# 10_SDADC.net
KiCad netlist of a schematic drawn in Altium Designer
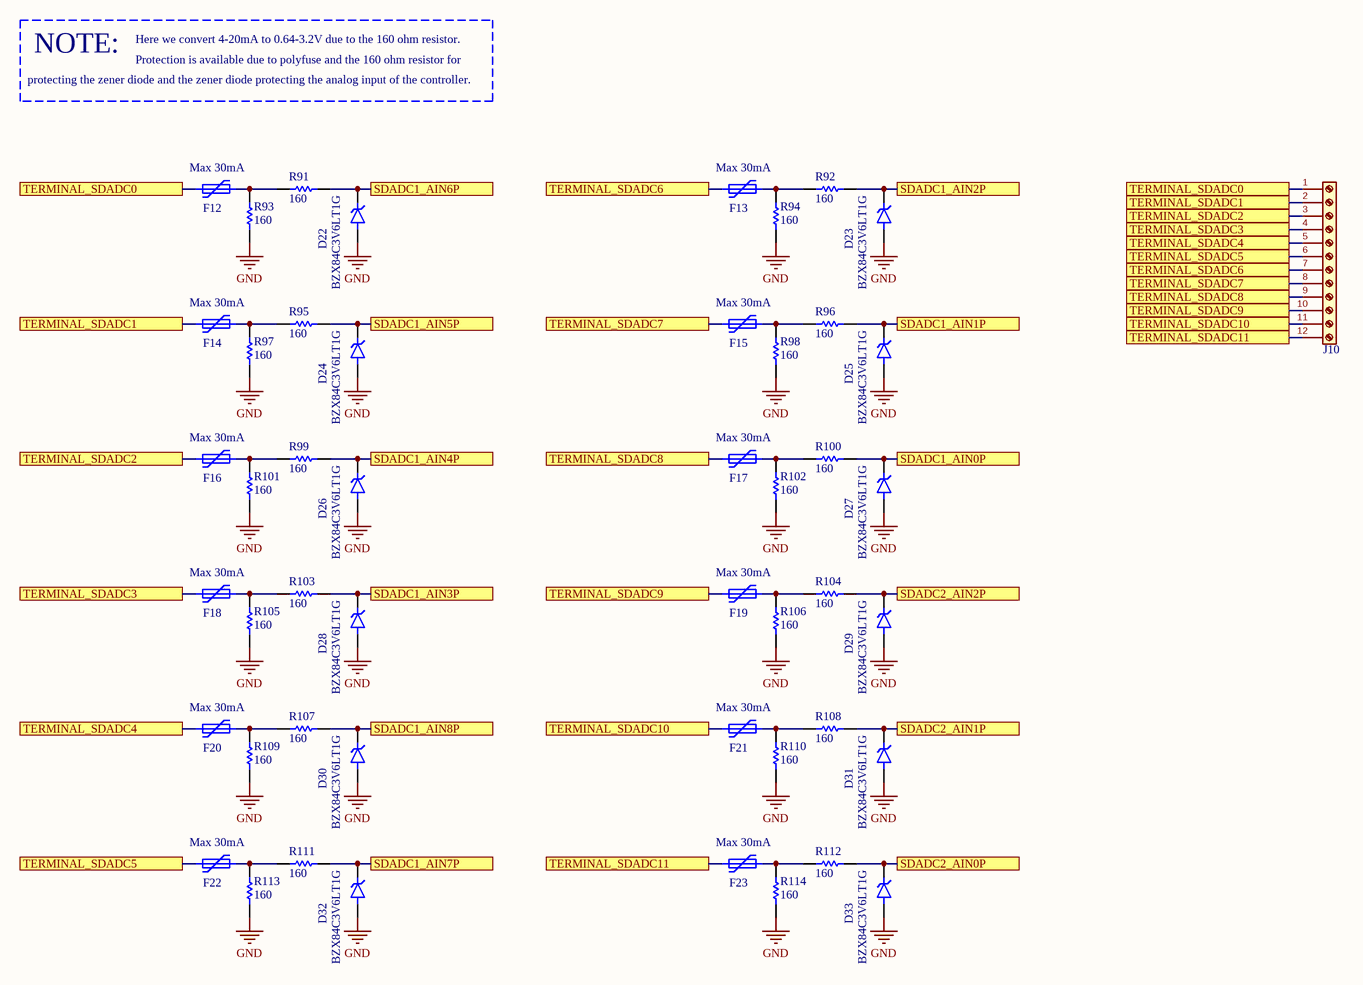
[diagram p0: 10_SDADC.SchDoc]

(export (version "E")
  (design (tool "Eeschema 10.0.6"))
  (components
    (comp (ref "D22")
      (value "BZX84C3V6LT1G")
      (footprint "SOT95P240X111-3N")
      (fields (field (name "MP") "BZX84C10LT1G"))
      (libsource (lib "PROC051C_AWR1843BOOST_RevC") (part "BZX84C3V6LT1G"))
    )
    (comp (ref "D23")
      (value "BZX84C3V6LT1G")
      (footprint "SOT95P240X111-3N")
      (fields (field (name "MP") "BZX84C10LT1G"))
      (libsource (lib "PROC051C_AWR1843BOOST_RevC") (part "BZX84C3V6LT1G"))
    )
    (comp (ref "D24")
      (value "BZX84C3V6LT1G")
      (footprint "SOT95P240X111-3N")
      (fields (field (name "MP") "BZX84C10LT1G"))
      (libsource (lib "PROC051C_AWR1843BOOST_RevC") (part "BZX84C3V6LT1G"))
    )
    (comp (ref "D25")
      (value "BZX84C3V6LT1G")
      (footprint "SOT95P240X111-3N")
      (fields (field (name "MP") "BZX84C10LT1G"))
      (libsource (lib "PROC051C_AWR1843BOOST_RevC") (part "BZX84C3V6LT1G"))
    )
    (comp (ref "D26")
      (value "BZX84C3V6LT1G")
      (footprint "SOT95P240X111-3N")
      (fields (field (name "MP") "BZX84C10LT1G"))
      (libsource (lib "PROC051C_AWR1843BOOST_RevC") (part "BZX84C3V6LT1G"))
    )
    (comp (ref "D27")
      (value "BZX84C3V6LT1G")
      (footprint "SOT95P240X111-3N")
      (fields (field (name "MP") "BZX84C10LT1G"))
      (libsource (lib "PROC051C_AWR1843BOOST_RevC") (part "BZX84C3V6LT1G"))
    )
    (comp (ref "D28")
      (value "BZX84C3V6LT1G")
      (footprint "SOT95P240X111-3N")
      (fields (field (name "MP") "BZX84C10LT1G"))
      (libsource (lib "PROC051C_AWR1843BOOST_RevC") (part "BZX84C3V6LT1G"))
    )
    (comp (ref "D29")
      (value "BZX84C3V6LT1G")
      (footprint "SOT95P240X111-3N")
      (fields (field (name "MP") "BZX84C10LT1G"))
      (libsource (lib "PROC051C_AWR1843BOOST_RevC") (part "BZX84C3V6LT1G"))
    )
    (comp (ref "D30")
      (value "BZX84C3V6LT1G")
      (footprint "SOT95P240X111-3N")
      (fields (field (name "MP") "BZX84C10LT1G"))
      (libsource (lib "PROC051C_AWR1843BOOST_RevC") (part "BZX84C3V6LT1G"))
    )
    (comp (ref "D31")
      (value "BZX84C3V6LT1G")
      (footprint "SOT95P240X111-3N")
      (fields (field (name "MP") "BZX84C10LT1G"))
      (libsource (lib "PROC051C_AWR1843BOOST_RevC") (part "BZX84C3V6LT1G"))
    )
    (comp (ref "D32")
      (value "BZX84C3V6LT1G")
      (footprint "SOT95P240X111-3N")
      (fields (field (name "MP") "BZX84C10LT1G"))
      (libsource (lib "PROC051C_AWR1843BOOST_RevC") (part "BZX84C3V6LT1G"))
    )
    (comp (ref "D33")
      (value "BZX84C3V6LT1G")
      (footprint "SOT95P240X111-3N")
      (fields (field (name "MP") "BZX84C10LT1G"))
      (libsource (lib "PROC051C_AWR1843BOOST_RevC") (part "BZX84C3V6LT1G"))
    )
    (comp (ref "F12")
      (value "Max 30mA")
      (footprint "Fuse_0603_1608Metric")
      (libsource (lib "PROC051C_AWR1843BOOST_RevC") (part "Polyfuse 0603"))
    )
    (comp (ref "F13")
      (value "Max 30mA")
      (footprint "Fuse_0603_1608Metric")
      (libsource (lib "PROC051C_AWR1843BOOST_RevC") (part "Polyfuse 0603"))
    )
    (comp (ref "F14")
      (value "Max 30mA")
      (footprint "Fuse_0603_1608Metric")
      (libsource (lib "PROC051C_AWR1843BOOST_RevC") (part "Polyfuse 0603"))
    )
    (comp (ref "F15")
      (value "Max 30mA")
      (footprint "Fuse_0603_1608Metric")
      (libsource (lib "PROC051C_AWR1843BOOST_RevC") (part "Polyfuse 0603"))
    )
    (comp (ref "F16")
      (value "Max 30mA")
      (footprint "Fuse_0603_1608Metric")
      (libsource (lib "PROC051C_AWR1843BOOST_RevC") (part "Polyfuse 0603"))
    )
    (comp (ref "F17")
      (value "Max 30mA")
      (footprint "Fuse_0603_1608Metric")
      (libsource (lib "PROC051C_AWR1843BOOST_RevC") (part "Polyfuse 0603"))
    )
    (comp (ref "F18")
      (value "Max 30mA")
      (footprint "Fuse_0603_1608Metric")
      (libsource (lib "PROC051C_AWR1843BOOST_RevC") (part "Polyfuse 0603"))
    )
    (comp (ref "F19")
      (value "Max 30mA")
      (footprint "Fuse_0603_1608Metric")
      (libsource (lib "PROC051C_AWR1843BOOST_RevC") (part "Polyfuse 0603"))
    )
    (comp (ref "F20")
      (value "Max 30mA")
      (footprint "Fuse_0603_1608Metric")
      (libsource (lib "PROC051C_AWR1843BOOST_RevC") (part "Polyfuse 0603"))
    )
    (comp (ref "F21")
      (value "Max 30mA")
      (footprint "Fuse_0603_1608Metric")
      (libsource (lib "PROC051C_AWR1843BOOST_RevC") (part "Polyfuse 0603"))
    )
    (comp (ref "F22")
      (value "Max 30mA")
      (footprint "Fuse_0603_1608Metric")
      (libsource (lib "PROC051C_AWR1843BOOST_RevC") (part "Polyfuse 0603"))
    )
    (comp (ref "F23")
      (value "Max 30mA")
      (footprint "Fuse_0603_1608Metric")
      (libsource (lib "PROC051C_AWR1843BOOST_RevC") (part "Polyfuse 0603"))
    )
    (comp (ref "J10")
      (value "Terminal_01x12_P5.00")
      (footprint "TerminalBlock_Phoenix_PT-1,5-12-5.0-H_1x12_P5.00mm_Horizontal")
      (libsource (lib "PROC051C_AWR1843BOOST_RevC") (part "Terminal_01x12_P5.00"))
    )
    (comp (ref "R91")
      (value "CRCW060320R0JNEA")
      (footprint "0603")
      (description "RES, 160, 5%, 0.1 W, AEC-Q200 Grade 0, 0603")
      (fields (field (name "MANUFACTURER") "Vishay-Dale") (field (name "VALUEDISPLAYED") "160"))
      (libsource (lib "PROC051C_AWR1843BOOST_RevC") (part "RES 160R 0603"))
    )
    (comp (ref "R92")
      (value "CRCW060320R0JNEA")
      (footprint "0603")
      (description "RES, 160, 5%, 0.1 W, AEC-Q200 Grade 0, 0603")
      (fields (field (name "MANUFACTURER") "Vishay-Dale") (field (name "VALUEDISPLAYED") "160"))
      (libsource (lib "PROC051C_AWR1843BOOST_RevC") (part "RES 160R 0603"))
    )
    (comp (ref "R93")
      (value "CRCW060320R0JNEA")
      (footprint "0603")
      (description "RES, 160, 5%, 0.1 W, AEC-Q200 Grade 0, 0603")
      (fields (field (name "MANUFACTURER") "Vishay-Dale") (field (name "VALUEDISPLAYED") "160"))
      (libsource (lib "PROC051C_AWR1843BOOST_RevC") (part "RES 160R 0603"))
    )
    (comp (ref "R94")
      (value "CRCW060320R0JNEA")
      (footprint "0603")
      (description "RES, 160, 5%, 0.1 W, AEC-Q200 Grade 0, 0603")
      (fields (field (name "MANUFACTURER") "Vishay-Dale") (field (name "VALUEDISPLAYED") "160"))
      (libsource (lib "PROC051C_AWR1843BOOST_RevC") (part "RES 160R 0603"))
    )
    (comp (ref "R95")
      (value "CRCW060320R0JNEA")
      (footprint "0603")
      (description "RES, 160, 5%, 0.1 W, AEC-Q200 Grade 0, 0603")
      (fields (field (name "MANUFACTURER") "Vishay-Dale") (field (name "VALUEDISPLAYED") "160"))
      (libsource (lib "PROC051C_AWR1843BOOST_RevC") (part "RES 160R 0603"))
    )
    (comp (ref "R96")
      (value "CRCW060320R0JNEA")
      (footprint "0603")
      (description "RES, 160, 5%, 0.1 W, AEC-Q200 Grade 0, 0603")
      (fields (field (name "MANUFACTURER") "Vishay-Dale") (field (name "VALUEDISPLAYED") "160"))
      (libsource (lib "PROC051C_AWR1843BOOST_RevC") (part "RES 160R 0603"))
    )
    (comp (ref "R97")
      (value "CRCW060320R0JNEA")
      (footprint "0603")
      (description "RES, 160, 5%, 0.1 W, AEC-Q200 Grade 0, 0603")
      (fields (field (name "MANUFACTURER") "Vishay-Dale") (field (name "VALUEDISPLAYED") "160"))
      (libsource (lib "PROC051C_AWR1843BOOST_RevC") (part "RES 160R 0603"))
    )
    (comp (ref "R98")
      (value "CRCW060320R0JNEA")
      (footprint "0603")
      (description "RES, 160, 5%, 0.1 W, AEC-Q200 Grade 0, 0603")
      (fields (field (name "MANUFACTURER") "Vishay-Dale") (field (name "VALUEDISPLAYED") "160"))
      (libsource (lib "PROC051C_AWR1843BOOST_RevC") (part "RES 160R 0603"))
    )
    (comp (ref "R99")
      (value "CRCW060320R0JNEA")
      (footprint "0603")
      (description "RES, 160, 5%, 0.1 W, AEC-Q200 Grade 0, 0603")
      (fields (field (name "MANUFACTURER") "Vishay-Dale") (field (name "VALUEDISPLAYED") "160"))
      (libsource (lib "PROC051C_AWR1843BOOST_RevC") (part "RES 160R 0603"))
    )
    (comp (ref "R100")
      (value "CRCW060320R0JNEA")
      (footprint "0603")
      (description "RES, 160, 5%, 0.1 W, AEC-Q200 Grade 0, 0603")
      (fields (field (name "MANUFACTURER") "Vishay-Dale") (field (name "VALUEDISPLAYED") "160"))
      (libsource (lib "PROC051C_AWR1843BOOST_RevC") (part "RES 160R 0603"))
    )
    (comp (ref "R101")
      (value "CRCW060320R0JNEA")
      (footprint "0603")
      (description "RES, 160, 5%, 0.1 W, AEC-Q200 Grade 0, 0603")
      (fields (field (name "MANUFACTURER") "Vishay-Dale") (field (name "VALUEDISPLAYED") "160"))
      (libsource (lib "PROC051C_AWR1843BOOST_RevC") (part "RES 160R 0603"))
    )
    (comp (ref "R102")
      (value "CRCW060320R0JNEA")
      (footprint "0603")
      (description "RES, 160, 5%, 0.1 W, AEC-Q200 Grade 0, 0603")
      (fields (field (name "MANUFACTURER") "Vishay-Dale") (field (name "VALUEDISPLAYED") "160"))
      (libsource (lib "PROC051C_AWR1843BOOST_RevC") (part "RES 160R 0603"))
    )
    (comp (ref "R103")
      (value "CRCW060320R0JNEA")
      (footprint "0603")
      (description "RES, 160, 5%, 0.1 W, AEC-Q200 Grade 0, 0603")
      (fields (field (name "MANUFACTURER") "Vishay-Dale") (field (name "VALUEDISPLAYED") "160"))
      (libsource (lib "PROC051C_AWR1843BOOST_RevC") (part "RES 160R 0603"))
    )
    (comp (ref "R104")
      (value "CRCW060320R0JNEA")
      (footprint "0603")
      (description "RES, 160, 5%, 0.1 W, AEC-Q200 Grade 0, 0603")
      (fields (field (name "MANUFACTURER") "Vishay-Dale") (field (name "VALUEDISPLAYED") "160"))
      (libsource (lib "PROC051C_AWR1843BOOST_RevC") (part "RES 160R 0603"))
    )
    (comp (ref "R105")
      (value "CRCW060320R0JNEA")
      (footprint "0603")
      (description "RES, 160, 5%, 0.1 W, AEC-Q200 Grade 0, 0603")
      (fields (field (name "MANUFACTURER") "Vishay-Dale") (field (name "VALUEDISPLAYED") "160"))
      (libsource (lib "PROC051C_AWR1843BOOST_RevC") (part "RES 160R 0603"))
    )
    (comp (ref "R106")
      (value "CRCW060320R0JNEA")
      (footprint "0603")
      (description "RES, 160, 5%, 0.1 W, AEC-Q200 Grade 0, 0603")
      (fields (field (name "MANUFACTURER") "Vishay-Dale") (field (name "VALUEDISPLAYED") "160"))
      (libsource (lib "PROC051C_AWR1843BOOST_RevC") (part "RES 160R 0603"))
    )
    (comp (ref "R107")
      (value "CRCW060320R0JNEA")
      (footprint "0603")
      (description "RES, 160, 5%, 0.1 W, AEC-Q200 Grade 0, 0603")
      (fields (field (name "MANUFACTURER") "Vishay-Dale") (field (name "VALUEDISPLAYED") "160"))
      (libsource (lib "PROC051C_AWR1843BOOST_RevC") (part "RES 160R 0603"))
    )
    (comp (ref "R108")
      (value "CRCW060320R0JNEA")
      (footprint "0603")
      (description "RES, 160, 5%, 0.1 W, AEC-Q200 Grade 0, 0603")
      (fields (field (name "MANUFACTURER") "Vishay-Dale") (field (name "VALUEDISPLAYED") "160"))
      (libsource (lib "PROC051C_AWR1843BOOST_RevC") (part "RES 160R 0603"))
    )
    (comp (ref "R109")
      (value "CRCW060320R0JNEA")
      (footprint "0603")
      (description "RES, 160, 5%, 0.1 W, AEC-Q200 Grade 0, 0603")
      (fields (field (name "MANUFACTURER") "Vishay-Dale") (field (name "VALUEDISPLAYED") "160"))
      (libsource (lib "PROC051C_AWR1843BOOST_RevC") (part "RES 160R 0603"))
    )
    (comp (ref "R110")
      (value "CRCW060320R0JNEA")
      (footprint "0603")
      (description "RES, 160, 5%, 0.1 W, AEC-Q200 Grade 0, 0603")
      (fields (field (name "MANUFACTURER") "Vishay-Dale") (field (name "VALUEDISPLAYED") "160"))
      (libsource (lib "PROC051C_AWR1843BOOST_RevC") (part "RES 160R 0603"))
    )
    (comp (ref "R111")
      (value "CRCW060320R0JNEA")
      (footprint "0603")
      (description "RES, 160, 5%, 0.1 W, AEC-Q200 Grade 0, 0603")
      (fields (field (name "MANUFACTURER") "Vishay-Dale") (field (name "VALUEDISPLAYED") "160"))
      (libsource (lib "PROC051C_AWR1843BOOST_RevC") (part "RES 160R 0603"))
    )
    (comp (ref "R112")
      (value "CRCW060320R0JNEA")
      (footprint "0603")
      (description "RES, 160, 5%, 0.1 W, AEC-Q200 Grade 0, 0603")
      (fields (field (name "MANUFACTURER") "Vishay-Dale") (field (name "VALUEDISPLAYED") "160"))
      (libsource (lib "PROC051C_AWR1843BOOST_RevC") (part "RES 160R 0603"))
    )
    (comp (ref "R113")
      (value "CRCW060320R0JNEA")
      (footprint "0603")
      (description "RES, 160, 5%, 0.1 W, AEC-Q200 Grade 0, 0603")
      (fields (field (name "MANUFACTURER") "Vishay-Dale") (field (name "VALUEDISPLAYED") "160"))
      (libsource (lib "PROC051C_AWR1843BOOST_RevC") (part "RES 160R 0603"))
    )
    (comp (ref "R114")
      (value "CRCW060320R0JNEA")
      (footprint "0603")
      (description "RES, 160, 5%, 0.1 W, AEC-Q200 Grade 0, 0603")
      (fields (field (name "MANUFACTURER") "Vishay-Dale") (field (name "VALUEDISPLAYED") "160"))
      (libsource (lib "PROC051C_AWR1843BOOST_RevC") (part "RES 160R 0603"))
    )
  )
  (nets
    (net (code "1") (name "/SDADC1_AIN0P") (class "Default")
      (node (ref "D27") (pin "3") (pinfunction "K_3") (pintype "passive"))
      (node (ref "R100") (pin "2") (pinfunction "2_2") (pintype "passive"))
    )
    (net (code "2") (name "/SDADC1_AIN1P") (class "Default")
      (node (ref "D25") (pin "3") (pinfunction "K_3") (pintype "passive"))
      (node (ref "R96") (pin "2") (pinfunction "2_2") (pintype "passive"))
    )
    (net (code "3") (name "/SDADC1_AIN2P") (class "Default")
      (node (ref "D23") (pin "3") (pinfunction "K_3") (pintype "passive"))
      (node (ref "R92") (pin "2") (pinfunction "2_2") (pintype "passive"))
    )
    (net (code "4") (name "/SDADC1_AIN3P") (class "Default")
      (node (ref "D28") (pin "3") (pinfunction "K_3") (pintype "passive"))
      (node (ref "R103") (pin "2") (pinfunction "2_2") (pintype "passive"))
    )
    (net (code "5") (name "/SDADC1_AIN4P") (class "Default")
      (node (ref "D26") (pin "3") (pinfunction "K_3") (pintype "passive"))
      (node (ref "R99") (pin "2") (pinfunction "2_2") (pintype "passive"))
    )
    (net (code "6") (name "/SDADC1_AIN5P") (class "Default")
      (node (ref "D24") (pin "3") (pinfunction "K_3") (pintype "passive"))
      (node (ref "R95") (pin "2") (pinfunction "2_2") (pintype "passive"))
    )
    (net (code "7") (name "/SDADC1_AIN6P") (class "Default")
      (node (ref "D22") (pin "3") (pinfunction "K_3") (pintype "passive"))
      (node (ref "R91") (pin "2") (pinfunction "2_2") (pintype "passive"))
    )
    (net (code "8") (name "/SDADC1_AIN7P") (class "Default")
      (node (ref "D32") (pin "3") (pinfunction "K_3") (pintype "passive"))
      (node (ref "R111") (pin "2") (pinfunction "2_2") (pintype "passive"))
    )
    (net (code "9") (name "/SDADC1_AIN8P") (class "Default")
      (node (ref "D30") (pin "3") (pinfunction "K_3") (pintype "passive"))
      (node (ref "R107") (pin "2") (pinfunction "2_2") (pintype "passive"))
    )
    (net (code "10") (name "/SDADC2_AIN0P") (class "Default")
      (node (ref "D33") (pin "3") (pinfunction "K_3") (pintype "passive"))
      (node (ref "R112") (pin "2") (pinfunction "2_2") (pintype "passive"))
    )
    (net (code "11") (name "/SDADC2_AIN1P") (class "Default")
      (node (ref "D31") (pin "3") (pinfunction "K_3") (pintype "passive"))
      (node (ref "R108") (pin "2") (pinfunction "2_2") (pintype "passive"))
    )
    (net (code "12") (name "/SDADC2_AIN2P") (class "Default")
      (node (ref "D29") (pin "3") (pinfunction "K_3") (pintype "passive"))
      (node (ref "R104") (pin "2") (pinfunction "2_2") (pintype "passive"))
    )
    (net (code "13") (name "/TERMINAL_SDADC0") (class "Default")
      (node (ref "F12") (pin "1") (pinfunction "1_1") (pintype "passive"))
      (node (ref "J10") (pin "1") (pinfunction "Pin_1_1") (pintype "passive"))
    )
    (net (code "14") (name "/TERMINAL_SDADC1") (class "Default")
      (node (ref "F14") (pin "1") (pinfunction "1_1") (pintype "passive"))
      (node (ref "J10") (pin "2") (pinfunction "Pin_2_2") (pintype "passive"))
    )
    (net (code "15") (name "/TERMINAL_SDADC2") (class "Default")
      (node (ref "F16") (pin "1") (pinfunction "1_1") (pintype "passive"))
      (node (ref "J10") (pin "3") (pinfunction "Pin_3_3") (pintype "passive"))
    )
    (net (code "16") (name "/TERMINAL_SDADC3") (class "Default")
      (node (ref "F18") (pin "1") (pinfunction "1_1") (pintype "passive"))
      (node (ref "J10") (pin "4") (pinfunction "Pin_4_4") (pintype "passive"))
    )
    (net (code "17") (name "/TERMINAL_SDADC4") (class "Default")
      (node (ref "F20") (pin "1") (pinfunction "1_1") (pintype "passive"))
      (node (ref "J10") (pin "5") (pinfunction "Pin_5_5") (pintype "passive"))
    )
    (net (code "18") (name "/TERMINAL_SDADC5") (class "Default")
      (node (ref "F22") (pin "1") (pinfunction "1_1") (pintype "passive"))
      (node (ref "J10") (pin "6") (pinfunction "Pin_6_6") (pintype "passive"))
    )
    (net (code "19") (name "/TERMINAL_SDADC6") (class "Default")
      (node (ref "F13") (pin "1") (pinfunction "1_1") (pintype "passive"))
      (node (ref "J10") (pin "7") (pinfunction "Pin_7_7") (pintype "passive"))
    )
    (net (code "20") (name "/TERMINAL_SDADC7") (class "Default")
      (node (ref "F15") (pin "1") (pinfunction "1_1") (pintype "passive"))
      (node (ref "J10") (pin "8") (pinfunction "Pin_8_8") (pintype "passive"))
    )
    (net (code "21") (name "/TERMINAL_SDADC8") (class "Default")
      (node (ref "F17") (pin "1") (pinfunction "1_1") (pintype "passive"))
      (node (ref "J10") (pin "9") (pinfunction "Pin_9_9") (pintype "passive"))
    )
    (net (code "22") (name "/TERMINAL_SDADC9") (class "Default")
      (node (ref "F19") (pin "1") (pinfunction "1_1") (pintype "passive"))
      (node (ref "J10") (pin "10") (pinfunction "Pin_10_10") (pintype "passive"))
    )
    (net (code "23") (name "/TERMINAL_SDADC10") (class "Default")
      (node (ref "F21") (pin "1") (pinfunction "1_1") (pintype "passive"))
      (node (ref "J10") (pin "11") (pinfunction "Pin_11_11") (pintype "passive"))
    )
    (net (code "24") (name "/TERMINAL_SDADC11") (class "Default")
      (node (ref "F23") (pin "1") (pinfunction "1_1") (pintype "passive"))
      (node (ref "J10") (pin "12") (pinfunction "Pin_12_12") (pintype "passive"))
    )
    (net (code "25") (name "GND") (class "Default")
      (node (ref "D22") (pin "1") (pinfunction "A_1") (pintype "passive"))
      (node (ref "D23") (pin "1") (pinfunction "A_1") (pintype "passive"))
      (node (ref "D24") (pin "1") (pinfunction "A_1") (pintype "passive"))
      (node (ref "D25") (pin "1") (pinfunction "A_1") (pintype "passive"))
      (node (ref "D26") (pin "1") (pinfunction "A_1") (pintype "passive"))
      (node (ref "D27") (pin "1") (pinfunction "A_1") (pintype "passive"))
      (node (ref "D28") (pin "1") (pinfunction "A_1") (pintype "passive"))
      (node (ref "D29") (pin "1") (pinfunction "A_1") (pintype "passive"))
      (node (ref "D30") (pin "1") (pinfunction "A_1") (pintype "passive"))
      (node (ref "D31") (pin "1") (pinfunction "A_1") (pintype "passive"))
      (node (ref "D32") (pin "1") (pinfunction "A_1") (pintype "passive"))
      (node (ref "D33") (pin "1") (pinfunction "A_1") (pintype "passive"))
      (node (ref "R101") (pin "1") (pinfunction "1_1") (pintype "passive"))
      (node (ref "R102") (pin "1") (pinfunction "1_1") (pintype "passive"))
      (node (ref "R105") (pin "1") (pinfunction "1_1") (pintype "passive"))
      (node (ref "R106") (pin "1") (pinfunction "1_1") (pintype "passive"))
      (node (ref "R109") (pin "1") (pinfunction "1_1") (pintype "passive"))
      (node (ref "R110") (pin "1") (pinfunction "1_1") (pintype "passive"))
      (node (ref "R113") (pin "1") (pinfunction "1_1") (pintype "passive"))
      (node (ref "R114") (pin "1") (pinfunction "1_1") (pintype "passive"))
      (node (ref "R93") (pin "1") (pinfunction "1_1") (pintype "passive"))
      (node (ref "R94") (pin "1") (pinfunction "1_1") (pintype "passive"))
      (node (ref "R97") (pin "1") (pinfunction "1_1") (pintype "passive"))
      (node (ref "R98") (pin "1") (pinfunction "1_1") (pintype "passive"))
    )
    (net (code "26") (name "Net-(F12-Pad2)") (class "Default")
      (node (ref "F12") (pin "2") (pinfunction "2_2") (pintype "passive"))
      (node (ref "R91") (pin "1") (pinfunction "1_1") (pintype "passive"))
      (node (ref "R93") (pin "2") (pinfunction "2_2") (pintype "passive"))
    )
    (net (code "27") (name "Net-(F13-Pad2)") (class "Default")
      (node (ref "F13") (pin "2") (pinfunction "2_2") (pintype "passive"))
      (node (ref "R92") (pin "1") (pinfunction "1_1") (pintype "passive"))
      (node (ref "R94") (pin "2") (pinfunction "2_2") (pintype "passive"))
    )
    (net (code "28") (name "Net-(F14-Pad2)") (class "Default")
      (node (ref "F14") (pin "2") (pinfunction "2_2") (pintype "passive"))
      (node (ref "R95") (pin "1") (pinfunction "1_1") (pintype "passive"))
      (node (ref "R97") (pin "2") (pinfunction "2_2") (pintype "passive"))
    )
    (net (code "29") (name "Net-(F15-Pad2)") (class "Default")
      (node (ref "F15") (pin "2") (pinfunction "2_2") (pintype "passive"))
      (node (ref "R96") (pin "1") (pinfunction "1_1") (pintype "passive"))
      (node (ref "R98") (pin "2") (pinfunction "2_2") (pintype "passive"))
    )
    (net (code "30") (name "Net-(F16-Pad2)") (class "Default")
      (node (ref "F16") (pin "2") (pinfunction "2_2") (pintype "passive"))
      (node (ref "R101") (pin "2") (pinfunction "2_2") (pintype "passive"))
      (node (ref "R99") (pin "1") (pinfunction "1_1") (pintype "passive"))
    )
    (net (code "31") (name "Net-(F17-Pad2)") (class "Default")
      (node (ref "F17") (pin "2") (pinfunction "2_2") (pintype "passive"))
      (node (ref "R100") (pin "1") (pinfunction "1_1") (pintype "passive"))
      (node (ref "R102") (pin "2") (pinfunction "2_2") (pintype "passive"))
    )
    (net (code "32") (name "Net-(F18-Pad2)") (class "Default")
      (node (ref "F18") (pin "2") (pinfunction "2_2") (pintype "passive"))
      (node (ref "R103") (pin "1") (pinfunction "1_1") (pintype "passive"))
      (node (ref "R105") (pin "2") (pinfunction "2_2") (pintype "passive"))
    )
    (net (code "33") (name "Net-(F19-Pad2)") (class "Default")
      (node (ref "F19") (pin "2") (pinfunction "2_2") (pintype "passive"))
      (node (ref "R104") (pin "1") (pinfunction "1_1") (pintype "passive"))
      (node (ref "R106") (pin "2") (pinfunction "2_2") (pintype "passive"))
    )
    (net (code "34") (name "Net-(F20-Pad2)") (class "Default")
      (node (ref "F20") (pin "2") (pinfunction "2_2") (pintype "passive"))
      (node (ref "R107") (pin "1") (pinfunction "1_1") (pintype "passive"))
      (node (ref "R109") (pin "2") (pinfunction "2_2") (pintype "passive"))
    )
    (net (code "35") (name "Net-(F21-Pad2)") (class "Default")
      (node (ref "F21") (pin "2") (pinfunction "2_2") (pintype "passive"))
      (node (ref "R108") (pin "1") (pinfunction "1_1") (pintype "passive"))
      (node (ref "R110") (pin "2") (pinfunction "2_2") (pintype "passive"))
    )
    (net (code "36") (name "Net-(F22-Pad2)") (class "Default")
      (node (ref "F22") (pin "2") (pinfunction "2_2") (pintype "passive"))
      (node (ref "R111") (pin "1") (pinfunction "1_1") (pintype "passive"))
      (node (ref "R113") (pin "2") (pinfunction "2_2") (pintype "passive"))
    )
    (net (code "37") (name "Net-(F23-Pad2)") (class "Default")
      (node (ref "F23") (pin "2") (pinfunction "2_2") (pintype "passive"))
      (node (ref "R112") (pin "1") (pinfunction "1_1") (pintype "passive"))
      (node (ref "R114") (pin "2") (pinfunction "2_2") (pintype "passive"))
    )
  )
)
